# pcb_file.net
KiCad netlist of a schematic drawn in EasyEDA Pro
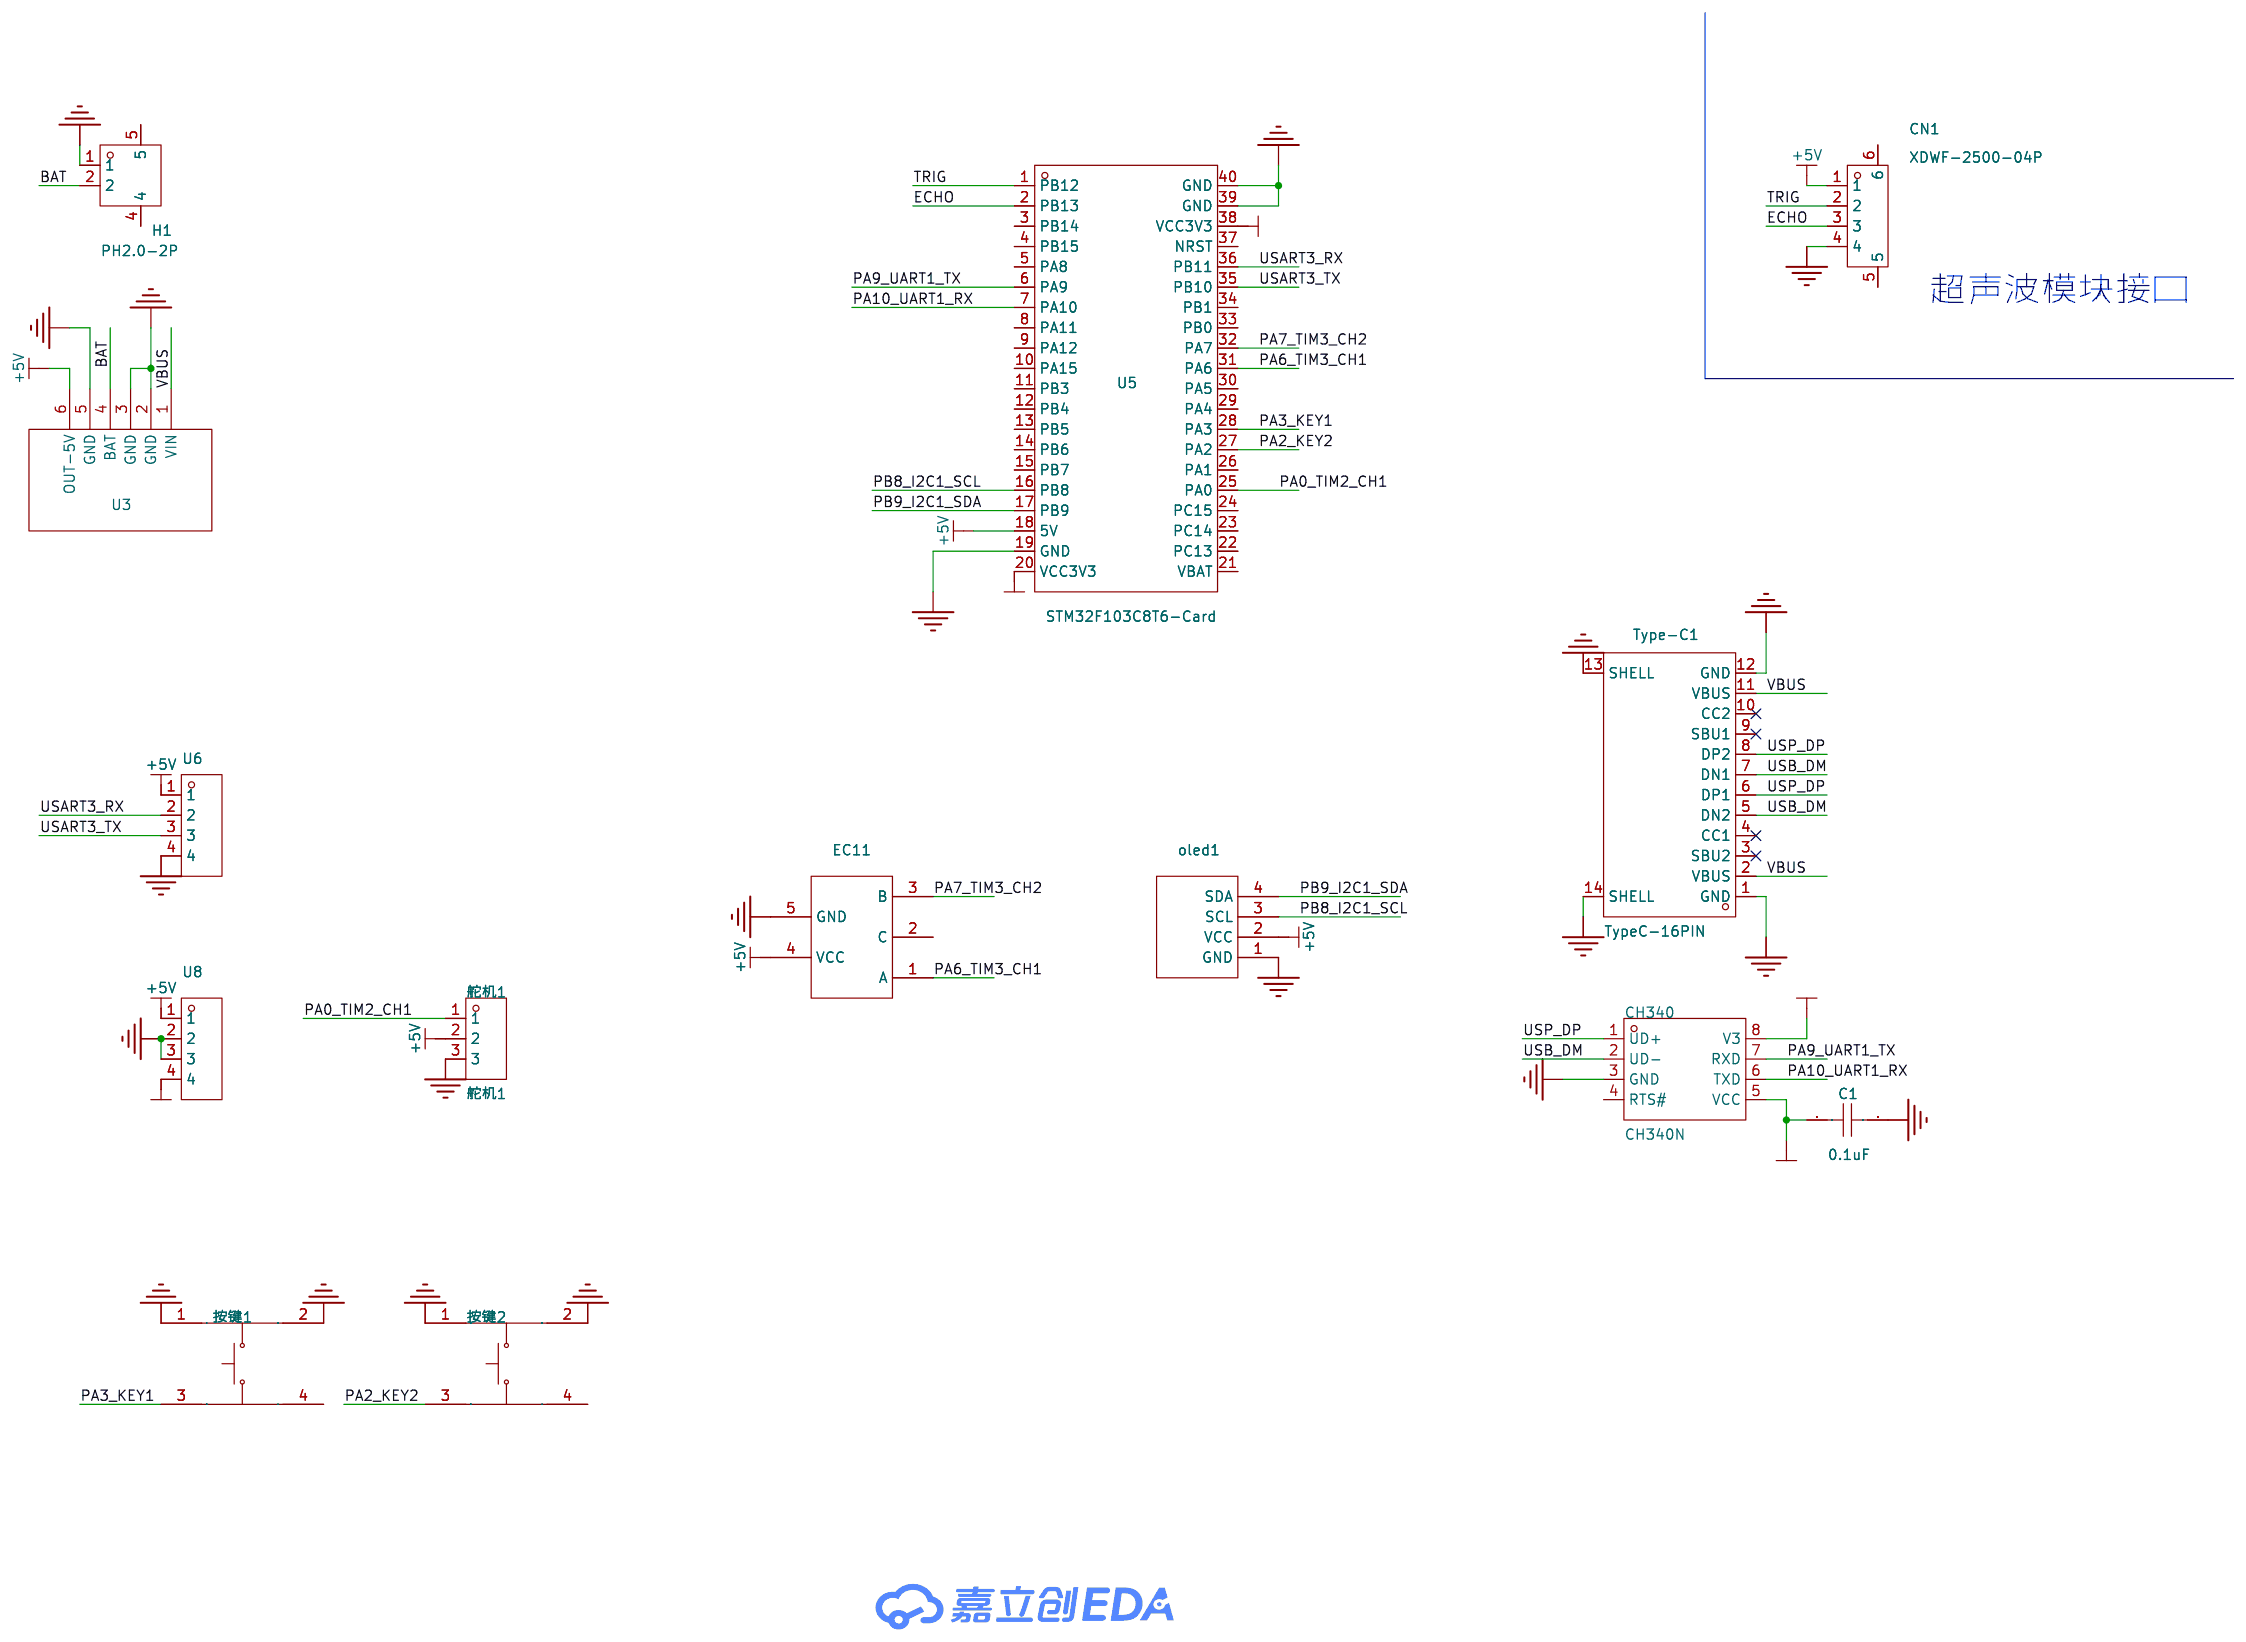
[diagram p0: schematic sheet]

(export (version "E")
  (design (tool "Eeschema 10.0.6"))
  (components
    (comp (ref "C1")
      (value "0.1uF")
      (footprint "easyedapro:C0805")
      (description "容值:22uF;精度:±20%;额定电压:25V;材质(温度系数):X5R;")
      (fields
        (field (name "Manufacturer Part") "CL21A226MAQNNNE")
        (field (name "Manufacturer") "SAMSUNG(三星)")
      )
      (libsource (lib "easyedapro") (part "CL21A226MAQNNNE"))
    )
    (comp (ref "CH340")
      (value "CH340N")
      (footprint "easyedapro:SOP-8_L4.9-W3.9-P1.27-LS6.0-BL")
      (fields (field (name "Manufacturer") "WCH(南京沁恒)"))
      (libsource (lib "easyedapro") (part "CH340N_C2977777"))
    )
    (comp (ref "CN1")
      (value "XDWF-2500-04P")
      (footprint "easyedapro:CONN-SMD_4P-P2.54_MXXH-2.54-04P-WT1-0-A")
      (description "间距:2.54mm;安装方式:卧贴;参考系列:XH;总PIN数:4P;额定电流:4A;工作温度范围:-40°C~+85°C;")
      (fields (field (name "Manufacturer") "LX(连欣科技)"))
      (libsource (lib "easyedapro") (part "XDWF-2500-04P"))
    )
    (comp (ref "EC11")
      (value "~")
      (footprint "easyedapro:EC11封装")
      (libsource (lib "easyedapro") (part "EC11"))
    )
    (comp (ref "H1")
      (value "PH2.0-2P")
      (footprint "easyedapro:CONN-SMD_2P-P2.00_XUNPU_WAFER-PH2.0-2PWB")
      (description "插针结构:1x2P;间距:2mm;安装方式:卧贴;总PIN数:2P;排数:1;每排PIN数:2;额定电流:2A;工作温度范围:-25°C~+85°C;")
      (fields (field (name "Manufacturer") "XUNPU(讯普)"))
      (libsource (lib "easyedapro") (part "WAFER-PH2.0-2PWB"))
    )
    (comp (ref "oled1")
      (value "~")
      (footprint "easyedapro:0.96 oled")
      (libsource (lib "easyedapro") (part "oled"))
    )
    (comp (ref "Type-C1")
      (value "TypeC-16PIN")
      (footprint "easyedapro:USB-C-SMD_TYPE-C-6PIN-2MD-073")
      (libsource (lib "easyedapro") (part "TYPEC-16PIN"))
    )
    (comp (ref "U3") (value "~") (footprint "easyedapro:充电板") (libsource (lib "easyedapro") (part "充电板")))
    (comp (ref "U5")
      (value "STM32F103C8T6-Card")
      (footprint "easyedapro:CONN-TH_L53.3-W22.9_STM32F103C8T6-CARD")
      (libsource (lib "easyedapro") (part "STM32F103C8T6-CARD"))
    )
    (comp (ref "U6")
      (value "FG-PM2.54-1-04P-H8.5")
      (footprint "easyedapro:CONN-TH_FG-PM2.54-1-04P-H8.5")
      (description "插孔结构:1x4P;间距:2.54mm;圆孔/方孔:方孔;安装方式:直插;排数:单排;总孔位数:4P;额定电流:3A;插孔方向:顶部;塑高:8.5mm;触头材质:黄铜;")
      (fields (field (name "Manufacturer") "FG(富港)"))
      (libsource (lib "easyedapro") (part "FG-PM2.54-1-04P-H8.5"))
    )
    (comp (ref "U8")
      (value "FG-PM2.54-1-04P-H8.5")
      (footprint "easyedapro:CONN-TH_FG-PM2.54-1-04P-H8.5")
      (description "插孔结构:1x4P;间距:2.54mm;圆孔/方孔:方孔;安装方式:直插;排数:单排;总孔位数:4P;额定电流:3A;插孔方向:顶部;塑高:8.5mm;触头材质:黄铜;")
      (fields (field (name "Manufacturer") "FG(富港)"))
      (libsource (lib "easyedapro") (part "FG-PM2.54-1-04P-H8.5"))
    )
    (comp (ref "按键1")
      (value "TS5215A 250gf")
      (footprint "easyedapro:SW-SMD_4P-L5.2-W5.2-P3.70-LS6.4")
      (description "电路结构:单刀单掷;按钮形状:圆形按钮;安装方式:立贴;开关长度:5.2mm;开关宽度:5.2mm;触点电流:50mA;额定电压(DC):12V;带灯:-;机械寿命:-;")
      (fields (field (name "Manufacturer") "SHOU HAN(首韩)"))
      (libsource (lib "easyedapro") (part "TS5215A 250GF"))
    )
    (comp (ref "按键2")
      (value "TS5215A 250gf")
      (footprint "easyedapro:SW-SMD_4P-L5.2-W5.2-P3.70-LS6.4")
      (description "电路结构:单刀单掷;按钮形状:圆形按钮;安装方式:立贴;开关长度:5.2mm;开关宽度:5.2mm;触点电流:50mA;额定电压(DC):12V;带灯:-;机械寿命:-;")
      (fields (field (name "Manufacturer") "SHOU HAN(首韩)"))
      (libsource (lib "easyedapro") (part "TS5215A 250GF"))
    )
    (comp (ref "舵机1")
      (value "舵机1")
      (fields (field (name "Manufacturer") "XFCN(兴飞)"))
      (libsource (lib "easyedapro") (part "PZ254V-11-03P_C2937625"))
    )
  )
  (nets
    (net (code "1") (name "+5V") (class "Default")
      (node (ref "CN1") (pin "1") (pinfunction "1_1") (pintype "unspecified"))
      (node (ref "EC11") (pin "4") (pinfunction "VCC_4") (pintype "input"))
      (node (ref "U3") (pin "6") (pinfunction "OUT-5V_6") (pintype "input"))
      (node (ref "U5") (pin "18") (pinfunction "5V_18") (pintype "unspecified"))
      (node (ref "U6") (pin "1") (pinfunction "1_1") (pintype "unspecified"))
      (node (ref "U8") (pin "1") (pinfunction "1_1") (pintype "unspecified"))
      (node (ref "oled1") (pin "2") (pinfunction "VCC_2") (pintype "input"))
      (node (ref "舵机1") (pin "2") (pinfunction "2_2") (pintype "unspecified"))
    )
    (net (code "2") (name "/BAT") (class "Default")
      (node (ref "H1") (pin "2") (pinfunction "2_2") (pintype "unspecified"))
      (node (ref "U3") (pin "4") (pinfunction "BAT_4") (pintype "input"))
    )
    (net (code "3") (name "/ECHO") (class "Default")
      (node (ref "CN1") (pin "3") (pinfunction "3_3") (pintype "unspecified"))
      (node (ref "U5") (pin "2") (pinfunction "PB13_2") (pintype "unspecified"))
    )
    (net (code "4") (name "/PA0_TIM2_CH1") (class "Default")
      (node (ref "U5") (pin "25") (pinfunction "PA0_25") (pintype "unspecified"))
      (node (ref "舵机1") (pin "1") (pinfunction "1_1") (pintype "unspecified"))
    )
    (net (code "5") (name "/PA2_KEY2") (class "Default")
      (node (ref "U5") (pin "27") (pinfunction "PA2_27") (pintype "unspecified"))
      (node (ref "按键2") (pin "3") (pinfunction "3_3") (pintype "unspecified"))
    )
    (net (code "6") (name "/PA3_KEY1") (class "Default")
      (node (ref "U5") (pin "28") (pinfunction "PA3_28") (pintype "unspecified"))
      (node (ref "按键1") (pin "3") (pinfunction "3_3") (pintype "unspecified"))
    )
    (net (code "7") (name "/PA6_TIM3_CH1") (class "Default")
      (node (ref "EC11") (pin "1") (pinfunction "A_1") (pintype "input"))
      (node (ref "U5") (pin "31") (pinfunction "PA6_31") (pintype "unspecified"))
    )
    (net (code "8") (name "/PA7_TIM3_CH2") (class "Default")
      (node (ref "EC11") (pin "3") (pinfunction "B_3") (pintype "input"))
      (node (ref "U5") (pin "32") (pinfunction "PA7_32") (pintype "unspecified"))
    )
    (net (code "9") (name "/PA9_UART1_TX") (class "Default")
      (node (ref "CH340") (pin "7") (pinfunction "RXD_7") (pintype "unspecified"))
      (node (ref "U5") (pin "6") (pinfunction "PA9_6") (pintype "unspecified"))
    )
    (net (code "10") (name "/PA10_UART1_RX") (class "Default")
      (node (ref "CH340") (pin "6") (pinfunction "TXD_6") (pintype "unspecified"))
      (node (ref "U5") (pin "7") (pinfunction "PA10_7") (pintype "unspecified"))
    )
    (net (code "11") (name "/PB8_I2C1_SCL") (class "Default")
      (node (ref "U5") (pin "16") (pinfunction "PB8_16") (pintype "unspecified"))
      (node (ref "oled1") (pin "3") (pinfunction "SCL_3") (pintype "input"))
    )
    (net (code "12") (name "/PB9_I2C1_SDA") (class "Default")
      (node (ref "U5") (pin "17") (pinfunction "PB9_17") (pintype "unspecified"))
      (node (ref "oled1") (pin "4") (pinfunction "SDA_4") (pintype "input"))
    )
    (net (code "13") (name "/TRIG") (class "Default")
      (node (ref "CN1") (pin "2") (pinfunction "2_2") (pintype "unspecified"))
      (node (ref "U5") (pin "1") (pinfunction "PB12_1") (pintype "unspecified"))
    )
    (net (code "14") (name "/USART3_RX") (class "Default")
      (node (ref "U5") (pin "36") (pinfunction "PB11_36") (pintype "unspecified"))
      (node (ref "U6") (pin "2") (pinfunction "2_2") (pintype "unspecified"))
    )
    (net (code "15") (name "/USART3_TX") (class "Default")
      (node (ref "U5") (pin "35") (pinfunction "PB10_35") (pintype "unspecified"))
      (node (ref "U6") (pin "3") (pinfunction "3_3") (pintype "unspecified"))
    )
    (net (code "16") (name "/USB_DM") (class "Default")
      (node (ref "CH340") (pin "2") (pinfunction "UD-_2") (pintype "unspecified"))
      (node (ref "Type-C1") (pin "5") (pinfunction "DN2_5") (pintype "input"))
      (node (ref "Type-C1") (pin "7") (pinfunction "DN1_7") (pintype "input"))
    )
    (net (code "17") (name "/USP_DP") (class "Default")
      (node (ref "CH340") (pin "1") (pinfunction "UD+_1") (pintype "unspecified"))
      (node (ref "Type-C1") (pin "6") (pinfunction "DP1_6") (pintype "input"))
      (node (ref "Type-C1") (pin "8") (pinfunction "DP2_8") (pintype "input"))
    )
    (net (code "18") (name "/VBUS") (class "Default")
      (node (ref "Type-C1") (pin "11") (pinfunction "VBUS_11") (pintype "input"))
      (node (ref "Type-C1") (pin "2") (pinfunction "VBUS_2") (pintype "input"))
      (node (ref "U3") (pin "1") (pinfunction "VIN_1") (pintype "input"))
    )
    (net (code "19") (name "3V3") (class "Default")
      (node (ref "C1") (pin "1") (pinfunction "1_1") (pintype "unspecified"))
      (node (ref "CH340") (pin "5") (pinfunction "VCC_5") (pintype "unspecified"))
      (node (ref "CH340") (pin "8") (pinfunction "V3_8") (pintype "unspecified"))
      (node (ref "U5") (pin "20") (pinfunction "VCC3V3_20") (pintype "unspecified"))
      (node (ref "U5") (pin "38") (pinfunction "VCC3V3_38") (pintype "unspecified"))
      (node (ref "U8") (pin "4") (pinfunction "4_4") (pintype "unspecified"))
    )
    (net (code "20") (name "GND") (class "Default")
      (node (ref "C1") (pin "2") (pinfunction "2_2") (pintype "unspecified"))
      (node (ref "CH340") (pin "3") (pinfunction "GND_3") (pintype "unspecified"))
      (node (ref "CN1") (pin "4") (pinfunction "4_4") (pintype "unspecified"))
      (node (ref "EC11") (pin "5") (pinfunction "GND_5") (pintype "input"))
      (node (ref "H1") (pin "1") (pinfunction "1_1") (pintype "unspecified"))
      (node (ref "Type-C1") (pin "1") (pinfunction "GND_1") (pintype "input"))
      (node (ref "Type-C1") (pin "12") (pinfunction "GND_12") (pintype "input"))
      (node (ref "Type-C1") (pin "13") (pinfunction "SHELL_13") (pintype "input"))
      (node (ref "Type-C1") (pin "14") (pinfunction "SHELL_14") (pintype "input"))
      (node (ref "U3") (pin "2") (pinfunction "GND_2") (pintype "input"))
      (node (ref "U3") (pin "3") (pinfunction "GND_3") (pintype "input"))
      (node (ref "U3") (pin "5") (pinfunction "GND_5") (pintype "input"))
      (node (ref "U5") (pin "19") (pinfunction "GND_19") (pintype "unspecified"))
      (node (ref "U5") (pin "39") (pinfunction "GND_39") (pintype "unspecified"))
      (node (ref "U5") (pin "40") (pinfunction "GND_40") (pintype "unspecified"))
      (node (ref "U6") (pin "4") (pinfunction "4_4") (pintype "unspecified"))
      (node (ref "U8") (pin "2") (pinfunction "2_2") (pintype "unspecified"))
      (node (ref "U8") (pin "3") (pinfunction "3_3") (pintype "unspecified"))
      (node (ref "oled1") (pin "1") (pinfunction "GND_1") (pintype "input"))
      (node (ref "按键1") (pin "1") (pinfunction "1_1") (pintype "unspecified"))
      (node (ref "按键1") (pin "2") (pinfunction "2_2") (pintype "unspecified"))
      (node (ref "按键2") (pin "1") (pinfunction "1_1") (pintype "unspecified"))
      (node (ref "按键2") (pin "2") (pinfunction "2_2") (pintype "unspecified"))
      (node (ref "舵机1") (pin "3") (pinfunction "3_3") (pintype "unspecified"))
    )
    (net (code "21") (name "unconnected-(CH340-RTS#-Pad4)") (class "Default")
      (node (ref "CH340") (pin "4") (pinfunction "RTS#_4") (pintype "unspecified"))
    )
    (net (code "22") (name "unconnected-(CN1-Pad5)") (class "Default")
      (node (ref "CN1") (pin "5") (pinfunction "5_5") (pintype "unspecified"))
    )
    (net (code "23") (name "unconnected-(CN1-Pad6)") (class "Default")
      (node (ref "CN1") (pin "6") (pinfunction "6_6") (pintype "unspecified"))
    )
    (net (code "24") (name "unconnected-(EC11-C-Pad2)") (class "Default")
      (node (ref "EC11") (pin "2") (pinfunction "C_2") (pintype "input"))
    )
    (net (code "25") (name "unconnected-(H1-Pad4)") (class "Default")
      (node (ref "H1") (pin "4") (pinfunction "4_4") (pintype "unspecified"))
    )
    (net (code "26") (name "unconnected-(H1-Pad5)") (class "Default")
      (node (ref "H1") (pin "5") (pinfunction "5_5") (pintype "unspecified"))
    )
    (net (code "27") (name "unconnected-(Type-C1-CC1-Pad4)") (class "Default")
      (node (ref "Type-C1") (pin "4") (pinfunction "CC1_4") (pintype "input+no_connect"))
    )
    (net (code "28") (name "unconnected-(Type-C1-CC2-Pad10)") (class "Default")
      (node (ref "Type-C1") (pin "10") (pinfunction "CC2_10") (pintype "input+no_connect"))
    )
    (net (code "29") (name "unconnected-(Type-C1-SBU1-Pad9)") (class "Default")
      (node (ref "Type-C1") (pin "9") (pinfunction "SBU1_9") (pintype "input+no_connect"))
    )
    (net (code "30") (name "unconnected-(Type-C1-SBU2-Pad3)") (class "Default")
      (node (ref "Type-C1") (pin "3") (pinfunction "SBU2_3") (pintype "input+no_connect"))
    )
    (net (code "31") (name "unconnected-(U5-NRST-Pad37)") (class "Default")
      (node (ref "U5") (pin "37") (pinfunction "NRST_37") (pintype "unspecified"))
    )
    (net (code "32") (name "unconnected-(U5-PA1-Pad26)") (class "Default")
      (node (ref "U5") (pin "26") (pinfunction "PA1_26") (pintype "unspecified"))
    )
    (net (code "33") (name "unconnected-(U5-PA4-Pad29)") (class "Default")
      (node (ref "U5") (pin "29") (pinfunction "PA4_29") (pintype "unspecified"))
    )
    (net (code "34") (name "unconnected-(U5-PA5-Pad30)") (class "Default")
      (node (ref "U5") (pin "30") (pinfunction "PA5_30") (pintype "unspecified"))
    )
    (net (code "35") (name "unconnected-(U5-PA8-Pad5)") (class "Default")
      (node (ref "U5") (pin "5") (pinfunction "PA8_5") (pintype "unspecified"))
    )
    (net (code "36") (name "unconnected-(U5-PA11-Pad8)") (class "Default")
      (node (ref "U5") (pin "8") (pinfunction "PA11_8") (pintype "unspecified"))
    )
    (net (code "37") (name "unconnected-(U5-PA12-Pad9)") (class "Default")
      (node (ref "U5") (pin "9") (pinfunction "PA12_9") (pintype "unspecified"))
    )
    (net (code "38") (name "unconnected-(U5-PA15-Pad10)") (class "Default")
      (node (ref "U5") (pin "10") (pinfunction "PA15_10") (pintype "unspecified"))
    )
    (net (code "39") (name "unconnected-(U5-PB0-Pad33)") (class "Default")
      (node (ref "U5") (pin "33") (pinfunction "PB0_33") (pintype "unspecified"))
    )
    (net (code "40") (name "unconnected-(U5-PB1-Pad34)") (class "Default")
      (node (ref "U5") (pin "34") (pinfunction "PB1_34") (pintype "unspecified"))
    )
    (net (code "41") (name "unconnected-(U5-PB3-Pad11)") (class "Default")
      (node (ref "U5") (pin "11") (pinfunction "PB3_11") (pintype "unspecified"))
    )
    (net (code "42") (name "unconnected-(U5-PB4-Pad12)") (class "Default")
      (node (ref "U5") (pin "12") (pinfunction "PB4_12") (pintype "unspecified"))
    )
    (net (code "43") (name "unconnected-(U5-PB5-Pad13)") (class "Default")
      (node (ref "U5") (pin "13") (pinfunction "PB5_13") (pintype "unspecified"))
    )
    (net (code "44") (name "unconnected-(U5-PB6-Pad14)") (class "Default")
      (node (ref "U5") (pin "14") (pinfunction "PB6_14") (pintype "unspecified"))
    )
    (net (code "45") (name "unconnected-(U5-PB7-Pad15)") (class "Default")
      (node (ref "U5") (pin "15") (pinfunction "PB7_15") (pintype "unspecified"))
    )
    (net (code "46") (name "unconnected-(U5-PB14-Pad3)") (class "Default")
      (node (ref "U5") (pin "3") (pinfunction "PB14_3") (pintype "unspecified"))
    )
    (net (code "47") (name "unconnected-(U5-PB15-Pad4)") (class "Default")
      (node (ref "U5") (pin "4") (pinfunction "PB15_4") (pintype "unspecified"))
    )
    (net (code "48") (name "unconnected-(U5-PC13-Pad22)") (class "Default")
      (node (ref "U5") (pin "22") (pinfunction "PC13_22") (pintype "unspecified"))
    )
    (net (code "49") (name "unconnected-(U5-PC14-Pad23)") (class "Default")
      (node (ref "U5") (pin "23") (pinfunction "PC14_23") (pintype "unspecified"))
    )
    (net (code "50") (name "unconnected-(U5-PC15-Pad24)") (class "Default")
      (node (ref "U5") (pin "24") (pinfunction "PC15_24") (pintype "unspecified"))
    )
    (net (code "51") (name "unconnected-(U5-VBAT-Pad21)") (class "Default")
      (node (ref "U5") (pin "21") (pinfunction "VBAT_21") (pintype "unspecified"))
    )
    (net (code "52") (name "unconnected-(按键1-Pad4)") (class "Default")
      (node (ref "按键1") (pin "4") (pinfunction "4_4") (pintype "unspecified"))
    )
    (net (code "53") (name "unconnected-(按键2-Pad4)") (class "Default")
      (node (ref "按键2") (pin "4") (pinfunction "4_4") (pintype "unspecified"))
    )
  )
)
